# USB-HUB.net
KiCad netlist of a schematic drawn in Altium Designer
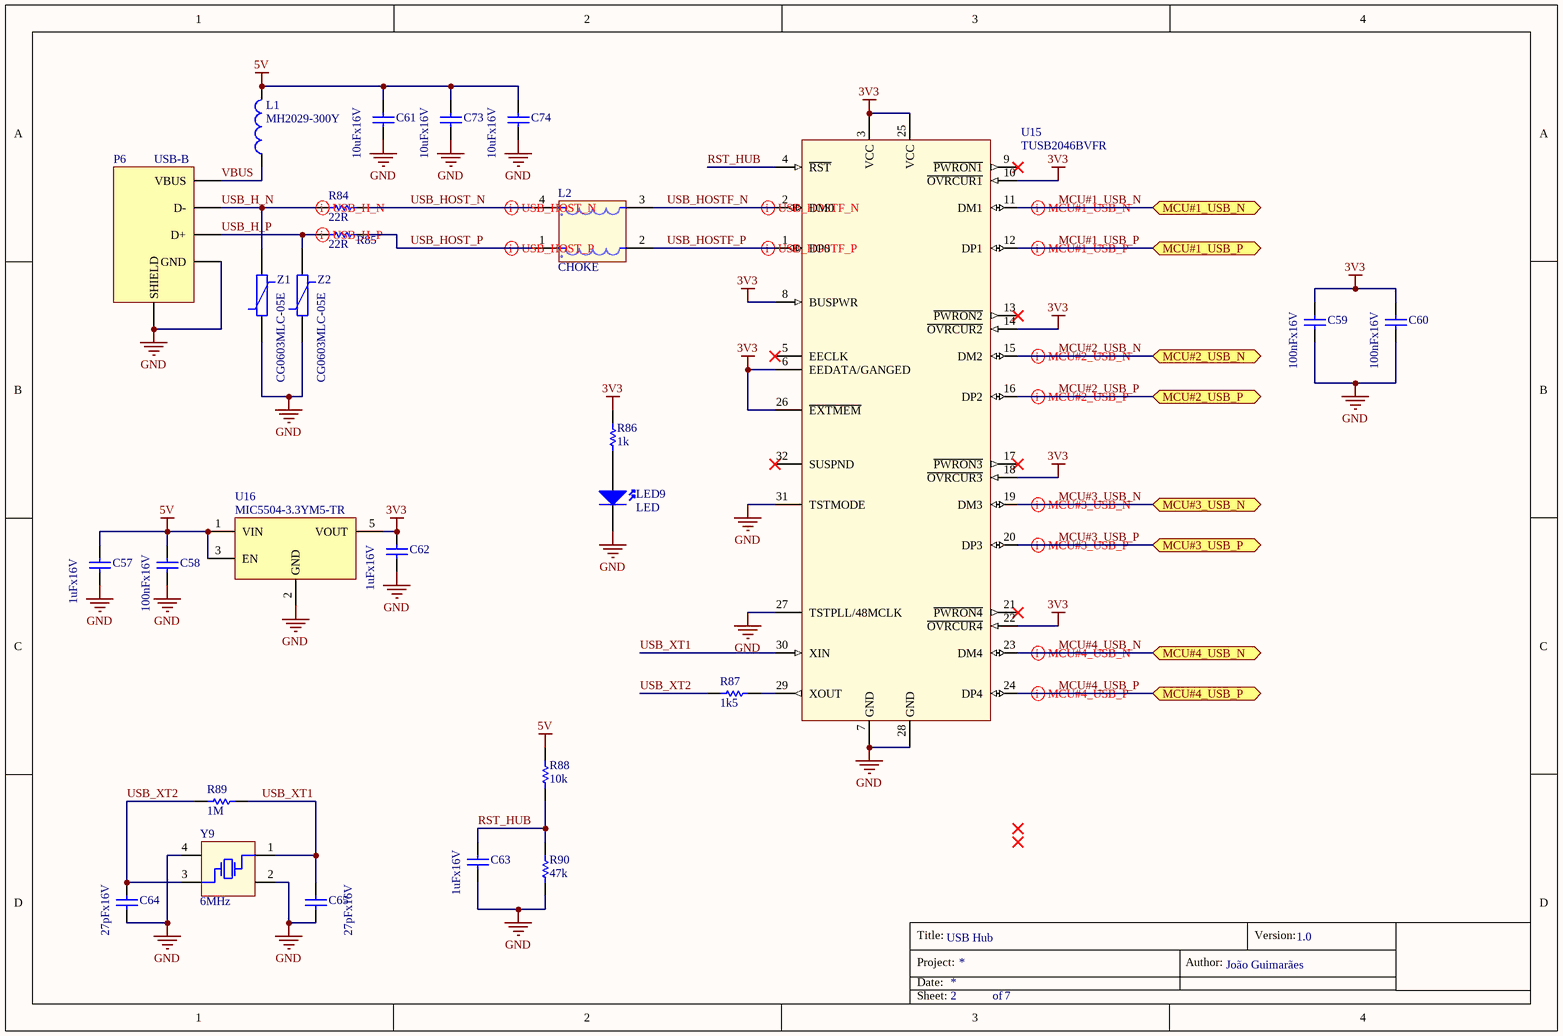
[diagram p0: USB-HUB.SchDoc]

(export (version "E")
  (design (tool "Eeschema 10.0.6"))
  (components
    (comp (ref "C57")
      (value "1uFx16V")
      (footprint "DISC-0603")
      (description "Capacitor")
      (libsource (lib "IntLib") (part "Cap"))
    )
    (comp (ref "C58")
      (value "100nFx16V")
      (footprint "DISC-0603")
      (description "Capacitor")
      (libsource (lib "IntLib") (part "Cap"))
    )
    (comp (ref "C59")
      (value "100nFx16V")
      (footprint "DISC-0603")
      (description "Capacitor")
      (libsource (lib "IntLib") (part "Cap"))
    )
    (comp (ref "C60")
      (value "100nFx16V")
      (footprint "DISC-0603")
      (description "Capacitor")
      (libsource (lib "IntLib") (part "Cap"))
    )
    (comp (ref "C61")
      (value "10uFx16V")
      (footprint "DISC-0805")
      (description "Capacitor")
      (libsource (lib "IntLib") (part "Cap"))
    )
    (comp (ref "C62")
      (value "1uFx16V")
      (footprint "DISC-0603")
      (description "Capacitor")
      (libsource (lib "IntLib") (part "Cap"))
    )
    (comp (ref "C63")
      (value "1uFx16V")
      (footprint "DISC-0603")
      (description "Capacitor")
      (libsource (lib "IntLib") (part "Cap"))
    )
    (comp (ref "C64")
      (value "27pFx16V")
      (footprint "DISC-0603")
      (description "Capacitor")
      (libsource (lib "IntLib") (part "Cap"))
    )
    (comp (ref "C65")
      (value "27pFx16V")
      (footprint "DISC-0603")
      (description "Capacitor")
      (libsource (lib "IntLib") (part "Cap"))
    )
    (comp (ref "C73")
      (value "10uFx16V")
      (footprint "DISC-0805")
      (description "Capacitor")
      (libsource (lib "IntLib") (part "Cap"))
    )
    (comp (ref "C74")
      (value "10uFx16V")
      (footprint "DISC-0805")
      (description "Capacitor")
      (libsource (lib "IntLib") (part "Cap"))
    )
    (comp (ref "L1")
      (value "MH2029-300Y")
      (footprint "DISC-0805")
      (description "Chip Inductor")
      (libsource (lib "IntLib") (part "Inductor"))
    )
    (comp (ref "L2")
      (value "CHOKE")
      (footprint "DISC-CHOKE-DLP11S")
      (description "Choke")
      (libsource (lib "IntLib") (part "Choke"))
    )
    (comp (ref "LED9") (value "LED") (footprint "DISC-LED-1206") (libsource (lib "IntLib") (part "LED")))
    (comp (ref "P6")
      (value "USB-B")
      (footprint "CON-USB-B")
      (description "USB Type-B")
      (libsource (lib "IntLib") (part "USB Type-B"))
    )
    (comp (ref "R84")
      (value "22R")
      (footprint "DISC-0603")
      (description "Resistor")
      (libsource (lib "IntLib") (part "Res"))
    )
    (comp (ref "R85")
      (value "22R")
      (footprint "DISC-0603")
      (description "Resistor")
      (libsource (lib "IntLib") (part "Res"))
    )
    (comp (ref "R86") (value "1k") (footprint "DISC-0603") (libsource (lib "IntLib") (part "Res")))
    (comp (ref "R87")
      (value "1k5")
      (footprint "DISC-0603")
      (description "Resistor")
      (libsource (lib "IntLib") (part "Res"))
    )
    (comp (ref "R88")
      (value "10k")
      (footprint "DISC-0603")
      (description "Resistor")
      (libsource (lib "IntLib") (part "Res"))
    )
    (comp (ref "R89")
      (value "1M")
      (footprint "DISC-0603")
      (description "Resistor")
      (libsource (lib "IntLib") (part "Res"))
    )
    (comp (ref "R90")
      (value "47k")
      (footprint "DISC-0603")
      (description "Resistor")
      (libsource (lib "IntLib") (part "Res"))
    )
    (comp (ref "U15")
      (value "TUSB2046BVFR")
      (footprint "CI-QFP-32")
      (description "TUSB2046x 4-Port Hub for the Universal Serial Bus With Optional\r\nSerial EEPROM Interface")
      (libsource (lib "IntLib") (part "TUSB2046BVFR"))
    )
    (comp (ref "U16")
      (value "MIC5504-3.3YM5-TR")
      (footprint "CI-SOT-23-5")
      (libsource (lib "IntLib") (part "MIC5504-3.3YM5-TR"))
    )
    (comp (ref "Y9")
      (value "6MHz")
      (footprint "DISC-CRYSTAL-4P-3.2X2.5")
      (description "XTAL-4-PIN")
      (libsource (lib "IntLib") (part "XTAL-4-PIN"))
    )
    (comp (ref "Z1")
      (value "CG0603MLC-05E")
      (footprint "DISC-0603")
      (description "Varistor")
      (libsource (lib "IntLib") (part "Varistor"))
    )
    (comp (ref "Z2")
      (value "CG0603MLC-05E")
      (footprint "DISC-0603")
      (description "Varistor")
      (libsource (lib "IntLib") (part "Varistor"))
    )
  )
  (nets
    (net (code "1") (name "/MCU#1_USB_N") (class "Default")
      (node (ref "U15") (pin "11") (pinfunction "DM1_11") (pintype "bidirectional"))
    )
    (net (code "2") (name "/MCU#1_USB_P") (class "Default")
      (node (ref "U15") (pin "12") (pinfunction "DP1_12") (pintype "bidirectional"))
    )
    (net (code "3") (name "/MCU#2_USB_N") (class "Default")
      (node (ref "U15") (pin "15") (pinfunction "DM2_15") (pintype "bidirectional"))
    )
    (net (code "4") (name "/MCU#2_USB_P") (class "Default")
      (node (ref "U15") (pin "16") (pinfunction "DP2_16") (pintype "bidirectional"))
    )
    (net (code "5") (name "/MCU#3_USB_N") (class "Default")
      (node (ref "U15") (pin "19") (pinfunction "DM3_19") (pintype "bidirectional"))
    )
    (net (code "6") (name "/MCU#3_USB_P") (class "Default")
      (node (ref "U15") (pin "20") (pinfunction "DP3_20") (pintype "bidirectional"))
    )
    (net (code "7") (name "/MCU#4_USB_N") (class "Default")
      (node (ref "U15") (pin "23") (pinfunction "DM4_23") (pintype "bidirectional"))
    )
    (net (code "8") (name "/MCU#4_USB_P") (class "Default")
      (node (ref "U15") (pin "24") (pinfunction "DP4_24") (pintype "bidirectional"))
    )
    (net (code "9") (name "/RST_HUB") (class "Default")
      (node (ref "C63") (pin "2") (pinfunction "2_2") (pintype "passive"))
      (node (ref "R88") (pin "2") (pinfunction "2_2") (pintype "passive"))
      (node (ref "R90") (pin "1") (pinfunction "1_1") (pintype "passive"))
      (node (ref "U15") (pin "4") (pinfunction "~{RST}_4") (pintype "input"))
    )
    (net (code "10") (name "/USB_HOSTF_N") (class "Default")
      (node (ref "L2") (pin "3") (pinfunction "3_3") (pintype "passive"))
      (node (ref "U15") (pin "2") (pinfunction "DM0_2") (pintype "bidirectional"))
    )
    (net (code "11") (name "/USB_HOSTF_P") (class "Default")
      (node (ref "L2") (pin "2") (pinfunction "2_2") (pintype "passive"))
      (node (ref "U15") (pin "1") (pinfunction "DP0_1") (pintype "bidirectional"))
    )
    (net (code "12") (name "/USB_HOST_N") (class "Default")
      (node (ref "L2") (pin "4") (pinfunction "4_4") (pintype "passive"))
      (node (ref "R84") (pin "2") (pinfunction "2_2") (pintype "passive"))
    )
    (net (code "13") (name "/USB_HOST_P") (class "Default")
      (node (ref "L2") (pin "1") (pinfunction "1_1") (pintype "passive"))
      (node (ref "R85") (pin "2") (pinfunction "2_2") (pintype "passive"))
    )
    (net (code "14") (name "/USB_H_N") (class "Default")
      (node (ref "P6") (pin "2") (pinfunction "D-_2") (pintype "passive"))
      (node (ref "R84") (pin "1") (pinfunction "1_1") (pintype "passive"))
      (node (ref "Z1") (pin "2") (pinfunction "2_2") (pintype "passive"))
    )
    (net (code "15") (name "/USB_H_P") (class "Default")
      (node (ref "P6") (pin "3") (pinfunction "D+_3") (pintype "passive"))
      (node (ref "R85") (pin "1") (pinfunction "1_1") (pintype "passive"))
      (node (ref "Z2") (pin "2") (pinfunction "2_2") (pintype "passive"))
    )
    (net (code "16") (name "/USB_XT1") (class "Default")
      (node (ref "C65") (pin "2") (pinfunction "2_2") (pintype "passive"))
      (node (ref "R89") (pin "2") (pinfunction "2_2") (pintype "passive"))
      (node (ref "U15") (pin "30") (pinfunction "XIN_30") (pintype "input"))
      (node (ref "Y9") (pin "1") (pinfunction "OSC1_1") (pintype "passive"))
    )
    (net (code "17") (name "/USB_XT2") (class "Default")
      (node (ref "C64") (pin "2") (pinfunction "2_2") (pintype "passive"))
      (node (ref "R87") (pin "1") (pinfunction "1_1") (pintype "passive"))
      (node (ref "R89") (pin "1") (pinfunction "1_1") (pintype "passive"))
      (node (ref "Y9") (pin "3") (pinfunction "OSC2_3") (pintype "passive"))
    )
    (net (code "18") (name "/VBUS") (class "Default")
      (node (ref "L1") (pin "1") (pinfunction "1_1") (pintype "passive"))
      (node (ref "P6") (pin "1") (pinfunction "VBUS_1") (pintype "passive"))
    )
    (net (code "19") (name "3V3") (class "Default")
      (node (ref "C59") (pin "1") (pinfunction "1_1") (pintype "passive"))
      (node (ref "C60") (pin "1") (pinfunction "1_1") (pintype "passive"))
      (node (ref "C62") (pin "1") (pinfunction "1_1") (pintype "passive"))
      (node (ref "R86") (pin "2") (pinfunction "2_2") (pintype "passive"))
      (node (ref "U15") (pin "10") (pinfunction "~{OVRCUR1}_10") (pintype "input"))
      (node (ref "U15") (pin "14") (pinfunction "~{OVRCUR2}_14") (pintype "input"))
      (node (ref "U15") (pin "18") (pinfunction "~{OVRCUR3}_18") (pintype "input"))
      (node (ref "U15") (pin "22") (pinfunction "~{OVRCUR4}_22") (pintype "input"))
      (node (ref "U15") (pin "25") (pinfunction "VCC_25") (pintype "power_in"))
      (node (ref "U15") (pin "26") (pinfunction "~{EXTMEM}_26") (pintype "passive"))
      (node (ref "U15") (pin "3") (pinfunction "VCC_3") (pintype "power_in"))
      (node (ref "U15") (pin "6") (pinfunction "EEDATA/GANGED_6") (pintype "passive"))
      (node (ref "U15") (pin "8") (pinfunction "BUSPWR_8") (pintype "input"))
      (node (ref "U16") (pin "5") (pinfunction "VOUT_5") (pintype "passive"))
    )
    (net (code "20") (name "5V") (class "Default")
      (node (ref "C57") (pin "1") (pinfunction "1_1") (pintype "passive"))
      (node (ref "C58") (pin "1") (pinfunction "1_1") (pintype "passive"))
      (node (ref "C61") (pin "1") (pinfunction "1_1") (pintype "passive"))
      (node (ref "C73") (pin "1") (pinfunction "1_1") (pintype "passive"))
      (node (ref "C74") (pin "1") (pinfunction "1_1") (pintype "passive"))
      (node (ref "L1") (pin "2") (pinfunction "2_2") (pintype "passive"))
      (node (ref "R88") (pin "1") (pinfunction "1_1") (pintype "passive"))
      (node (ref "U16") (pin "1") (pinfunction "VIN_1") (pintype "power_in"))
      (node (ref "U16") (pin "3") (pinfunction "EN_3") (pintype "power_in"))
    )
    (net (code "21") (name "GND") (class "Default")
      (node (ref "C57") (pin "2") (pinfunction "2_2") (pintype "passive"))
      (node (ref "C58") (pin "2") (pinfunction "2_2") (pintype "passive"))
      (node (ref "C59") (pin "2") (pinfunction "2_2") (pintype "passive"))
      (node (ref "C60") (pin "2") (pinfunction "2_2") (pintype "passive"))
      (node (ref "C61") (pin "2") (pinfunction "2_2") (pintype "passive"))
      (node (ref "C62") (pin "2") (pinfunction "2_2") (pintype "passive"))
      (node (ref "C63") (pin "1") (pinfunction "1_1") (pintype "passive"))
      (node (ref "C64") (pin "1") (pinfunction "1_1") (pintype "passive"))
      (node (ref "C65") (pin "1") (pinfunction "1_1") (pintype "passive"))
      (node (ref "C73") (pin "2") (pinfunction "2_2") (pintype "passive"))
      (node (ref "C74") (pin "2") (pinfunction "2_2") (pintype "passive"))
      (node (ref "LED9") (pin "2") (pinfunction "K_2") (pintype "passive"))
      (node (ref "P6") (pin "4") (pinfunction "GND_4") (pintype "passive"))
      (node (ref "P6") (pin "5") (pinfunction "SHIELD_5") (pintype "passive"))
      (node (ref "P6") (pin "6") (pinfunction "SHIELD_6") (pintype "passive"))
      (node (ref "R90") (pin "2") (pinfunction "2_2") (pintype "passive"))
      (node (ref "U15") (pin "27") (pinfunction "TSTPLL/48MCLK_27") (pintype "passive"))
      (node (ref "U15") (pin "28") (pinfunction "GND_28") (pintype "power_in"))
      (node (ref "U15") (pin "31") (pinfunction "TSTMODE_31") (pintype "passive"))
      (node (ref "U15") (pin "7") (pinfunction "GND_7") (pintype "power_in"))
      (node (ref "U16") (pin "2") (pinfunction "GND_2") (pintype "power_in"))
      (node (ref "Y9") (pin "2") (pinfunction "GND_2") (pintype "passive"))
      (node (ref "Y9") (pin "4") (pinfunction "GND_4") (pintype "passive"))
      (node (ref "Z1") (pin "1") (pinfunction "1_1") (pintype "passive"))
      (node (ref "Z2") (pin "1") (pinfunction "1_1") (pintype "passive"))
    )
    (net (code "22") (name "Net-(LED9-A)") (class "Default")
      (node (ref "LED9") (pin "1") (pinfunction "A_1") (pintype "passive"))
      (node (ref "R86") (pin "1") (pinfunction "1_1") (pintype "passive"))
    )
    (net (code "23") (name "Net-(U15-XOUT)") (class "Default")
      (node (ref "R87") (pin "2") (pinfunction "2_2") (pintype "passive"))
      (node (ref "U15") (pin "29") (pinfunction "XOUT_29") (pintype "output"))
    )
    (net (code "24") (name "unconnected-(U15-EECLK-Pad5)") (class "Default")
      (node (ref "U15") (pin "5") (pinfunction "EECLK_5") (pintype "passive+no_connect"))
    )
    (net (code "25") (name "unconnected-(U15-SUSPND-Pad32)") (class "Default")
      (node (ref "U15") (pin "32") (pinfunction "SUSPND_32") (pintype "passive+no_connect"))
    )
    (net (code "26") (name "unconnected-(U15-~{PWRON1}-Pad9)") (class "Default")
      (node (ref "U15") (pin "9") (pinfunction "~{PWRON1}_9") (pintype "output+no_connect"))
    )
    (net (code "27") (name "unconnected-(U15-~{PWRON2}-Pad13)") (class "Default")
      (node (ref "U15") (pin "13") (pinfunction "~{PWRON2}_13") (pintype "output+no_connect"))
    )
    (net (code "28") (name "unconnected-(U15-~{PWRON3}-Pad17)") (class "Default")
      (node (ref "U15") (pin "17") (pinfunction "~{PWRON3}_17") (pintype "output+no_connect"))
    )
    (net (code "29") (name "unconnected-(U15-~{PWRON4}-Pad21)") (class "Default")
      (node (ref "U15") (pin "21") (pinfunction "~{PWRON4}_21") (pintype "output+no_connect"))
    )
  )
)
